# InputsConnectors.net
KiCad netlist of a schematic drawn in Altium Designer
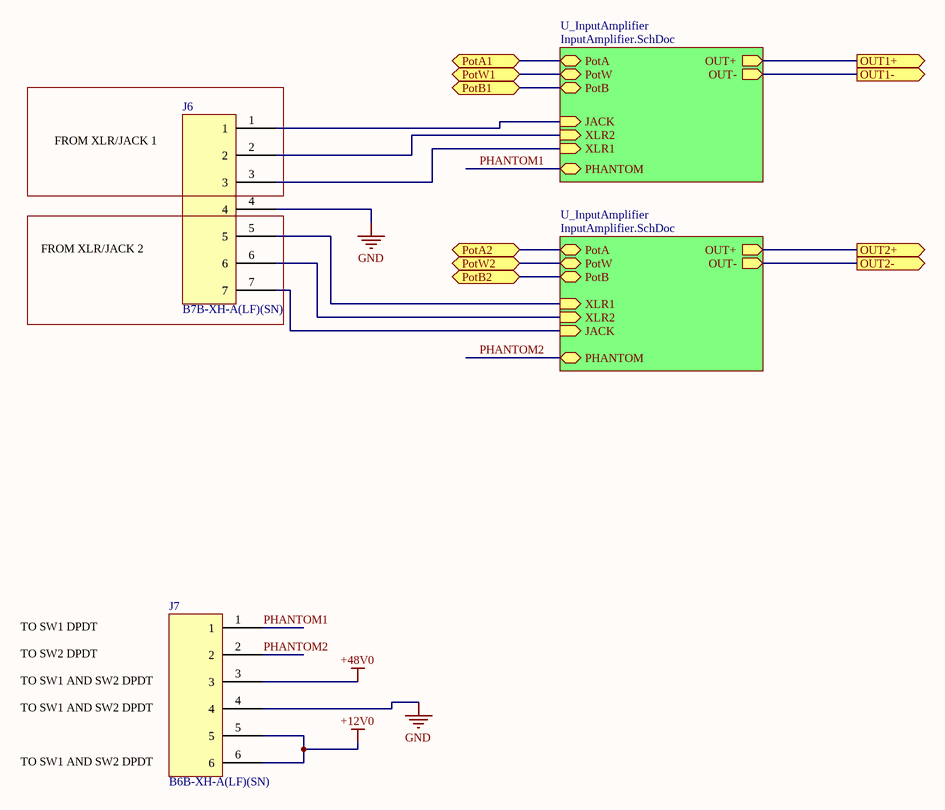
[diagram p0: InputsConnectors.SchDoc]

(export (version "E")
  (design (tool "Eeschema 10.0.6"))
  (components
    (comp (ref "J6")
      (value "B7B-XH-A(LF)(SN)")
      (footprint "CONN_7_HEADER")
      (fields (field (name "MFG") "JST Sales America Inc."))
      (libsource (lib "LIB_ADAPTONE_PASCAL_LEMIEUX") (part "CON_XH_JST_7pins"))
    )
    (comp (ref "J7")
      (value "CON_XH_JST_6pins")
      (footprint "CONN_6_HEADER")
      (fields (field (name "MFG") "JST Sales America Inc.") (field (name "MFG_PN") "B6B-XH-A(LF)(SN)"))
      (libsource (lib "LIB_ADAPTONE_PASCAL_LEMIEUX") (part "CON_XH_JST_6pins"))
    )
  )
  (nets
    (net (code "1") (name "+12V0") (class "Default")
      (node (ref "J7") (pin "5") (pinfunction "5_5") (pintype "passive"))
      (node (ref "J7") (pin "6") (pinfunction "6_6") (pintype "passive"))
    )
    (net (code "2") (name "+48V0") (class "Default")
      (node (ref "J7") (pin "3") (pinfunction "3_3") (pintype "passive"))
    )
    (net (code "3") (name "/JACK") (class "Default")
      (node (ref "J6") (pin "1") (pinfunction "1_1") (pintype "passive"))
    )
    (net (code "4") (name "/JACK_1") (class "Default")
      (node (ref "J6") (pin "7") (pinfunction "7_7") (pintype "passive"))
    )
    (net (code "9") (name "/PHANTOM1") (class "Default")
      (node (ref "J7") (pin "1") (pinfunction "1_1") (pintype "passive"))
    )
    (net (code "10") (name "/PHANTOM2") (class "Default")
      (node (ref "J7") (pin "2") (pinfunction "2_2") (pintype "passive"))
    )
    (net (code "17") (name "/XLR1") (class "Default")
      (node (ref "J6") (pin "5") (pinfunction "5_5") (pintype "passive"))
    )
    (net (code "18") (name "/XLR1_1") (class "Default")
      (node (ref "J6") (pin "3") (pinfunction "3_3") (pintype "passive"))
    )
    (net (code "19") (name "/XLR2") (class "Default")
      (node (ref "J6") (pin "6") (pinfunction "6_6") (pintype "passive"))
    )
    (net (code "20") (name "/XLR2_1") (class "Default")
      (node (ref "J6") (pin "2") (pinfunction "2_2") (pintype "passive"))
    )
    (net (code "21") (name "GND") (class "Default")
      (node (ref "J6") (pin "4") (pinfunction "4_4") (pintype "passive"))
      (node (ref "J7") (pin "4") (pinfunction "4_4") (pintype "passive"))
    )
  )
)
